# uController.net
KiCad netlist of a schematic drawn in Altium Designer
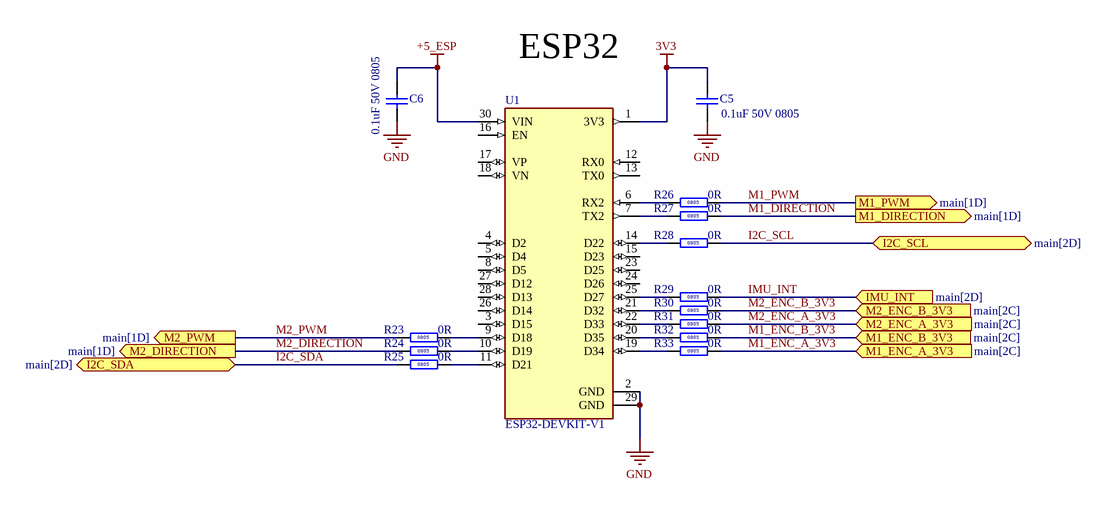
[diagram p0: uController.SchDoc]

(export (version "E")
  (design (tool "Eeschema 10.0.6"))
  (components
    (comp (ref "C5")
      (value "0.1uF 50V 0805")
      (footprint "CAPC2012X14N")
      (description "Cap, SMD, 0.1uF, 50V, 10%, 0805, X7R")
      (fields
        (field (name "MANUFACTURER") "Samsung")
        (field (name "MANUFACTURERPARTNUMBER") "CL21B104KBCWPNC")
      )
      (libsource (lib "Andor Technology") (part "CAP"))
    )
    (comp (ref "C6")
      (value "0.1uF 50V 0805")
      (footprint "CAPC2012X14N")
      (description "Cap, SMD, 0.1uF, 50V, 10%, 0805, X7R")
      (fields
        (field (name "MANUFACTURER") "Samsung")
        (field (name "MANUFACTURERPARTNUMBER") "CL21B104KBCWPNC")
      )
      (libsource (lib "Andor Technology") (part "CAP"))
    )
    (comp (ref "R23")
      (value "0R")
      (footprint "Copy of RESC2013X60X35NL10T20")
      (description "Res, SMD, 0R, 0.125W, 1%, 0805")
      (fields (field (name "MANUFACTURER") "Yageo") (field (name "MANUFACTURERPARTNUMBER") "RC0805JR-070RL"))
      (libsource (lib "Andor Technology") (part "Resistor_0805"))
    )
    (comp (ref "R24")
      (value "0R")
      (footprint "Copy of RESC2013X60X35NL10T20")
      (description "Res, SMD, 0R, 0.125W, 1%, 0805")
      (fields (field (name "MANUFACTURER") "Yageo") (field (name "MANUFACTURERPARTNUMBER") "RC0805JR-070RL"))
      (libsource (lib "Andor Technology") (part "Resistor_0805"))
    )
    (comp (ref "R25")
      (value "0R")
      (footprint "Copy of RESC2013X60X35NL10T20")
      (description "Res, SMD, 0R, 0.125W, 1%, 0805")
      (fields (field (name "MANUFACTURER") "Yageo") (field (name "MANUFACTURERPARTNUMBER") "RC0805JR-070RL"))
      (libsource (lib "Andor Technology") (part "Resistor_0805"))
    )
    (comp (ref "R26")
      (value "0R")
      (footprint "Copy of RESC2013X60X35NL10T20")
      (description "Res, SMD, 0R, 0.125W, 1%, 0805")
      (fields (field (name "MANUFACTURER") "Yageo") (field (name "MANUFACTURERPARTNUMBER") "RC0805JR-070RL"))
      (libsource (lib "Andor Technology") (part "Resistor_0805"))
    )
    (comp (ref "R27")
      (value "0R")
      (footprint "Copy of RESC2013X60X35NL10T20")
      (description "Res, SMD, 0R, 0.125W, 1%, 0805")
      (fields (field (name "MANUFACTURER") "Yageo") (field (name "MANUFACTURERPARTNUMBER") "RC0805JR-070RL"))
      (libsource (lib "Andor Technology") (part "Resistor_0805"))
    )
    (comp (ref "R28")
      (value "0R")
      (footprint "Copy of RESC2013X60X35NL10T20")
      (description "Res, SMD, 0R, 0.125W, 1%, 0805")
      (fields (field (name "MANUFACTURER") "Yageo") (field (name "MANUFACTURERPARTNUMBER") "RC0805JR-070RL"))
      (libsource (lib "Andor Technology") (part "Resistor_0805"))
    )
    (comp (ref "R29")
      (value "0R")
      (footprint "Copy of RESC2013X60X35NL10T20")
      (description "Res, SMD, 0R, 0.125W, 1%, 0805")
      (fields (field (name "MANUFACTURER") "Yageo") (field (name "MANUFACTURERPARTNUMBER") "RC0805JR-070RL"))
      (libsource (lib "Andor Technology") (part "Resistor_0805"))
    )
    (comp (ref "R30")
      (value "0R")
      (footprint "Copy of RESC2013X60X35NL10T20")
      (description "Res, SMD, 0R, 0.125W, 1%, 0805")
      (fields (field (name "MANUFACTURER") "Yageo") (field (name "MANUFACTURERPARTNUMBER") "RC0805JR-070RL"))
      (libsource (lib "Andor Technology") (part "Resistor_0805"))
    )
    (comp (ref "R31")
      (value "0R")
      (footprint "Copy of RESC2013X60X35NL10T20")
      (description "Res, SMD, 0R, 0.125W, 1%, 0805")
      (fields (field (name "MANUFACTURER") "Yageo") (field (name "MANUFACTURERPARTNUMBER") "RC0805JR-070RL"))
      (libsource (lib "Andor Technology") (part "Resistor_0805"))
    )
    (comp (ref "R32")
      (value "0R")
      (footprint "Copy of RESC2013X60X35NL10T20")
      (description "Res, SMD, 0R, 0.125W, 1%, 0805")
      (fields (field (name "MANUFACTURER") "Yageo") (field (name "MANUFACTURERPARTNUMBER") "RC0805JR-070RL"))
      (libsource (lib "Andor Technology") (part "Resistor_0805"))
    )
    (comp (ref "R33")
      (value "0R")
      (footprint "Copy of RESC2013X60X35NL10T20")
      (description "Res, SMD, 0R, 0.125W, 1%, 0805")
      (fields (field (name "MANUFACTURER") "Yageo") (field (name "MANUFACTURERPARTNUMBER") "RC0805JR-070RL"))
      (libsource (lib "Andor Technology") (part "Resistor_0805"))
    )
    (comp (ref "U1")
      (value "ESP32-DEVKIT-V1")
      (footprint "MODULE_ESP32_DEVKIT_V1")
      (fields (field (name "MF") "Do it"))
      (libsource (lib "ESP32-DEVKIT-V1") (part "ESP32-DEVKIT-V1"))
    )
  )
  (nets
    (net (code "1") (name "+5_ESP") (class "Default")
      (node (ref "C6") (pin "2") (pinfunction "2_2") (pintype "passive"))
      (node (ref "U1") (pin "30") (pinfunction "VIN_30") (pintype "input"))
    )
    (net (code "2") (name "/I2C_SCL") (class "Default")
      (node (ref "R28") (pin "2") (pinfunction "2_2") (pintype "passive"))
    )
    (net (code "3") (name "/I2C_SDA") (class "Default")
      (node (ref "R25") (pin "1") (pinfunction "1_1") (pintype "passive"))
    )
    (net (code "4") (name "/IMU_INT") (class "Default")
      (node (ref "R29") (pin "2") (pinfunction "2_2") (pintype "passive"))
    )
    (net (code "5") (name "/M1_DIRECTION") (class "Default")
      (node (ref "R27") (pin "2") (pinfunction "2_2") (pintype "passive"))
    )
    (net (code "6") (name "/M1_ENC_A_3V3") (class "Default")
      (node (ref "R33") (pin "2") (pinfunction "2_2") (pintype "passive"))
    )
    (net (code "7") (name "/M1_ENC_B_3V3") (class "Default")
      (node (ref "R32") (pin "2") (pinfunction "2_2") (pintype "passive"))
    )
    (net (code "8") (name "/M1_PWM") (class "Default")
      (node (ref "R26") (pin "2") (pinfunction "2_2") (pintype "passive"))
    )
    (net (code "9") (name "/M2_DIRECTION") (class "Default")
      (node (ref "R24") (pin "1") (pinfunction "1_1") (pintype "passive"))
    )
    (net (code "10") (name "/M2_ENC_A_3V3") (class "Default")
      (node (ref "R31") (pin "2") (pinfunction "2_2") (pintype "passive"))
    )
    (net (code "11") (name "/M2_ENC_B_3V3") (class "Default")
      (node (ref "R30") (pin "2") (pinfunction "2_2") (pintype "passive"))
    )
    (net (code "12") (name "/M2_PWM") (class "Default")
      (node (ref "R23") (pin "1") (pinfunction "1_1") (pintype "passive"))
    )
    (net (code "13") (name "3V3") (class "Default")
      (node (ref "C5") (pin "2") (pinfunction "2_2") (pintype "passive"))
      (node (ref "U1") (pin "1") (pinfunction "3V3_1") (pintype "output"))
    )
    (net (code "14") (name "GND") (class "Default")
      (node (ref "C5") (pin "1") (pinfunction "1_1") (pintype "passive"))
      (node (ref "C6") (pin "1") (pinfunction "1_1") (pintype "passive"))
      (node (ref "U1") (pin "2") (pinfunction "GND_2") (pintype "power_in"))
      (node (ref "U1") (pin "29") (pinfunction "GND_29") (pintype "power_in"))
    )
    (net (code "15") (name "Net-(U1-D18)") (class "Default")
      (node (ref "R23") (pin "2") (pinfunction "2_2") (pintype "passive"))
      (node (ref "U1") (pin "9") (pinfunction "D18_9") (pintype "bidirectional"))
    )
    (net (code "16") (name "Net-(U1-D19)") (class "Default")
      (node (ref "R24") (pin "2") (pinfunction "2_2") (pintype "passive"))
      (node (ref "U1") (pin "10") (pinfunction "D19_10") (pintype "bidirectional"))
    )
    (net (code "17") (name "Net-(U1-D21)") (class "Default")
      (node (ref "R25") (pin "2") (pinfunction "2_2") (pintype "passive"))
      (node (ref "U1") (pin "11") (pinfunction "D21_11") (pintype "bidirectional"))
    )
    (net (code "18") (name "Net-(U1-D22)") (class "Default")
      (node (ref "R28") (pin "1") (pinfunction "1_1") (pintype "passive"))
      (node (ref "U1") (pin "14") (pinfunction "D22_14") (pintype "bidirectional"))
    )
    (net (code "19") (name "Net-(U1-D27)") (class "Default")
      (node (ref "R29") (pin "1") (pinfunction "1_1") (pintype "passive"))
      (node (ref "U1") (pin "25") (pinfunction "D27_25") (pintype "bidirectional"))
    )
    (net (code "20") (name "Net-(U1-D32)") (class "Default")
      (node (ref "R30") (pin "1") (pinfunction "1_1") (pintype "passive"))
      (node (ref "U1") (pin "21") (pinfunction "D32_21") (pintype "bidirectional"))
    )
    (net (code "21") (name "Net-(U1-D33)") (class "Default")
      (node (ref "R31") (pin "1") (pinfunction "1_1") (pintype "passive"))
      (node (ref "U1") (pin "22") (pinfunction "D33_22") (pintype "bidirectional"))
    )
    (net (code "22") (name "Net-(U1-D34)") (class "Default")
      (node (ref "R33") (pin "1") (pinfunction "1_1") (pintype "passive"))
      (node (ref "U1") (pin "19") (pinfunction "D34_19") (pintype "bidirectional"))
    )
    (net (code "23") (name "Net-(U1-D35)") (class "Default")
      (node (ref "R32") (pin "1") (pinfunction "1_1") (pintype "passive"))
      (node (ref "U1") (pin "20") (pinfunction "D35_20") (pintype "bidirectional"))
    )
    (net (code "24") (name "Net-(U1-RX2)") (class "Default")
      (node (ref "R26") (pin "1") (pinfunction "1_1") (pintype "passive"))
      (node (ref "U1") (pin "6") (pinfunction "RX2_6") (pintype "input"))
    )
    (net (code "25") (name "Net-(U1-TX2)") (class "Default")
      (node (ref "R27") (pin "1") (pinfunction "1_1") (pintype "passive"))
      (node (ref "U1") (pin "7") (pinfunction "TX2_7") (pintype "output"))
    )
    (net (code "26") (name "unconnected-(U1-D2-Pad4)") (class "Default")
      (node (ref "U1") (pin "4") (pinfunction "D2_4") (pintype "bidirectional"))
    )
    (net (code "27") (name "unconnected-(U1-D4-Pad5)") (class "Default")
      (node (ref "U1") (pin "5") (pinfunction "D4_5") (pintype "bidirectional"))
    )
    (net (code "28") (name "unconnected-(U1-D5-Pad8)") (class "Default")
      (node (ref "U1") (pin "8") (pinfunction "D5_8") (pintype "bidirectional"))
    )
    (net (code "29") (name "unconnected-(U1-D12-Pad27)") (class "Default")
      (node (ref "U1") (pin "27") (pinfunction "D12_27") (pintype "bidirectional"))
    )
    (net (code "30") (name "unconnected-(U1-D13-Pad28)") (class "Default")
      (node (ref "U1") (pin "28") (pinfunction "D13_28") (pintype "bidirectional"))
    )
    (net (code "31") (name "unconnected-(U1-D14-Pad26)") (class "Default")
      (node (ref "U1") (pin "26") (pinfunction "D14_26") (pintype "bidirectional"))
    )
    (net (code "32") (name "unconnected-(U1-D15-Pad3)") (class "Default")
      (node (ref "U1") (pin "3") (pinfunction "D15_3") (pintype "bidirectional"))
    )
    (net (code "33") (name "unconnected-(U1-D23-Pad15)") (class "Default")
      (node (ref "U1") (pin "15") (pinfunction "D23_15") (pintype "bidirectional"))
    )
    (net (code "34") (name "unconnected-(U1-D25-Pad23)") (class "Default")
      (node (ref "U1") (pin "23") (pinfunction "D25_23") (pintype "bidirectional"))
    )
    (net (code "35") (name "unconnected-(U1-D26-Pad24)") (class "Default")
      (node (ref "U1") (pin "24") (pinfunction "D26_24") (pintype "bidirectional"))
    )
    (net (code "36") (name "unconnected-(U1-EN-Pad16)") (class "Default")
      (node (ref "U1") (pin "16") (pinfunction "EN_16") (pintype "input"))
    )
    (net (code "37") (name "unconnected-(U1-RX0-Pad12)") (class "Default")
      (node (ref "U1") (pin "12") (pinfunction "RX0_12") (pintype "input"))
    )
    (net (code "38") (name "unconnected-(U1-TX0-Pad13)") (class "Default")
      (node (ref "U1") (pin "13") (pinfunction "TX0_13") (pintype "output"))
    )
    (net (code "39") (name "unconnected-(U1-VN-Pad18)") (class "Default")
      (node (ref "U1") (pin "18") (pinfunction "VN_18") (pintype "bidirectional"))
    )
    (net (code "40") (name "unconnected-(U1-VP-Pad17)") (class "Default")
      (node (ref "U1") (pin "17") (pinfunction "VP_17") (pintype "bidirectional"))
    )
  )
)
